# smart_hub_v2.net
KiCad netlist of a schematic drawn in EAGLE
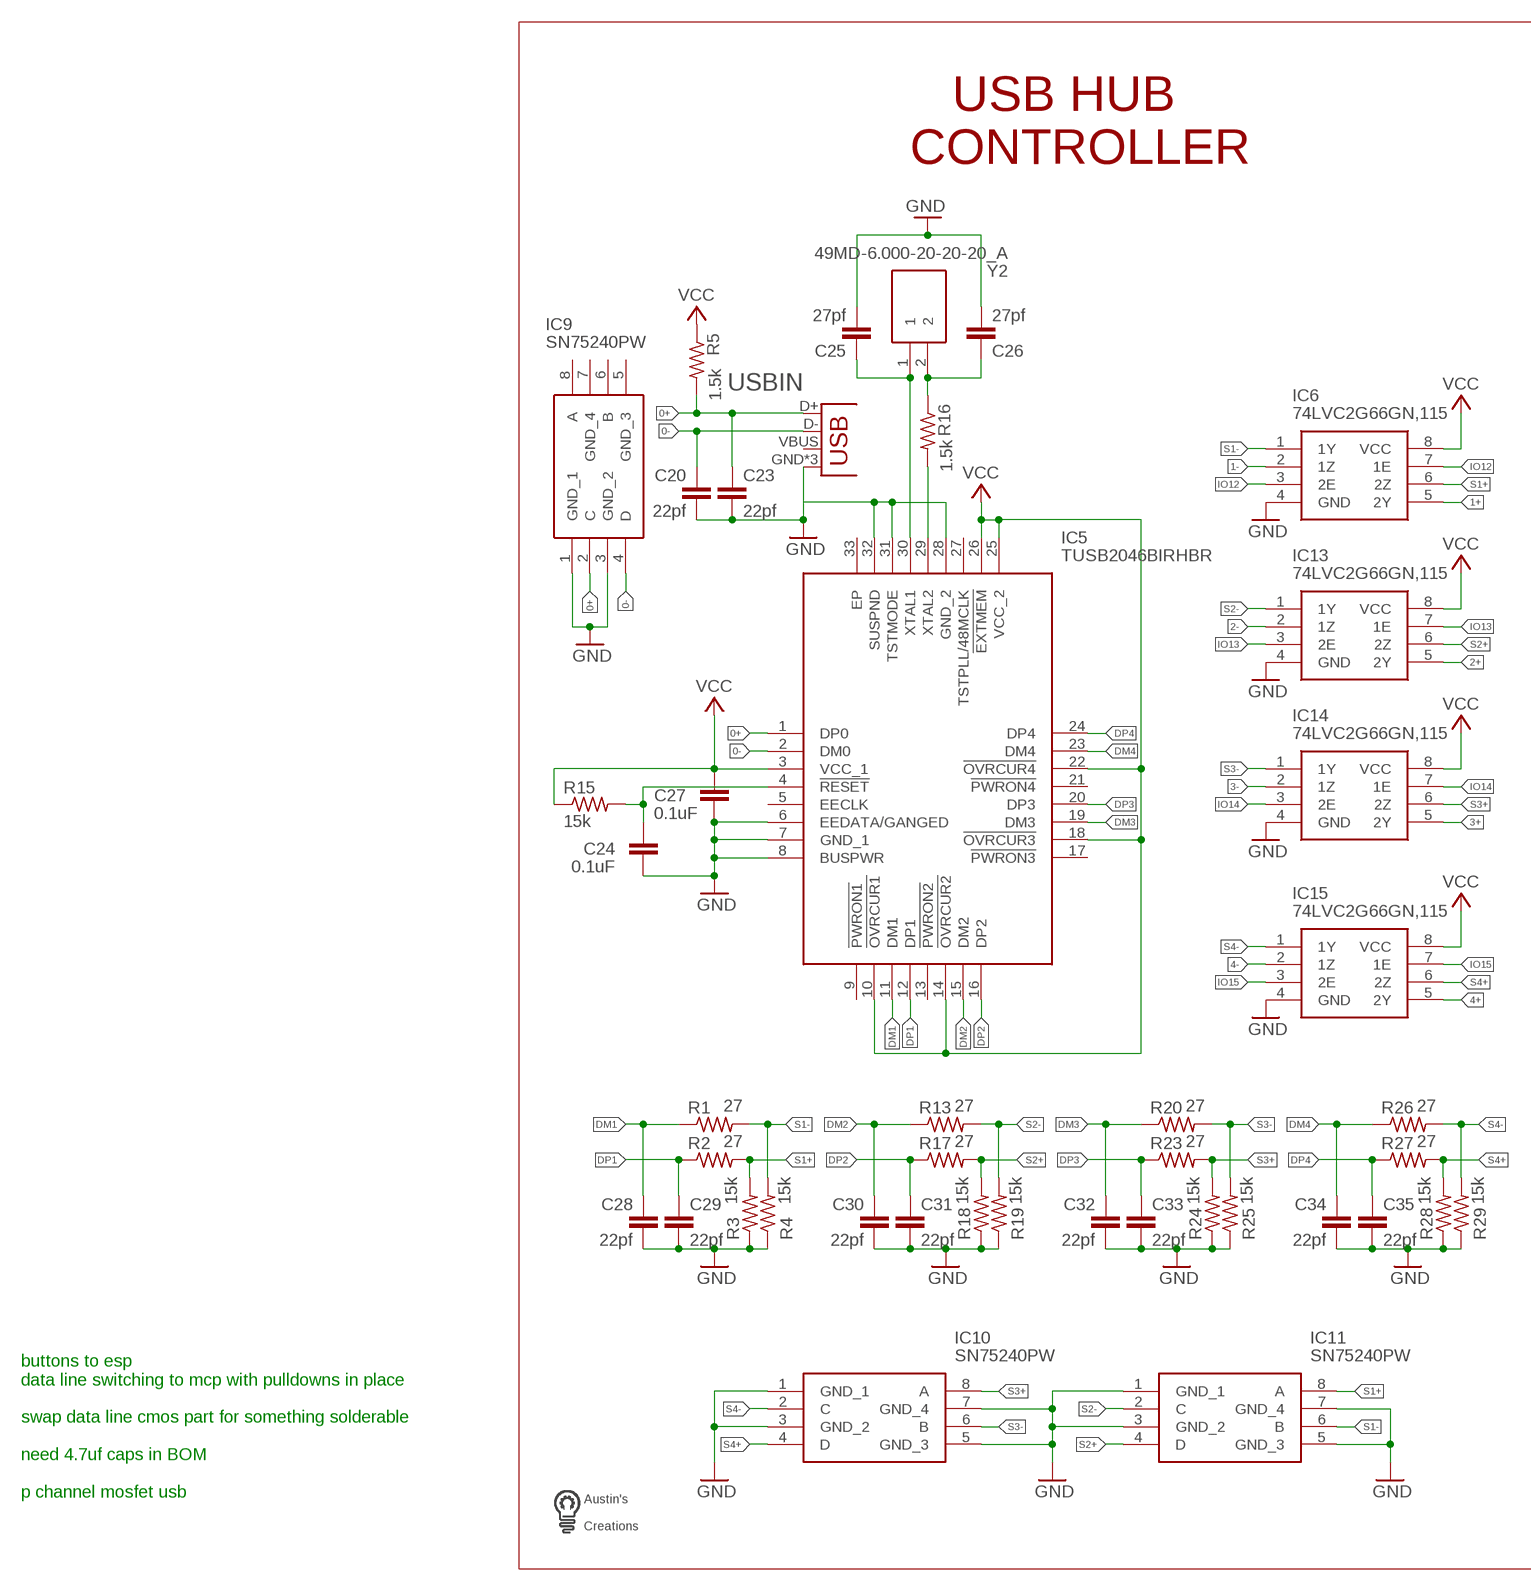
[diagram p0: schematic, sheet 1, part 1 of 2]
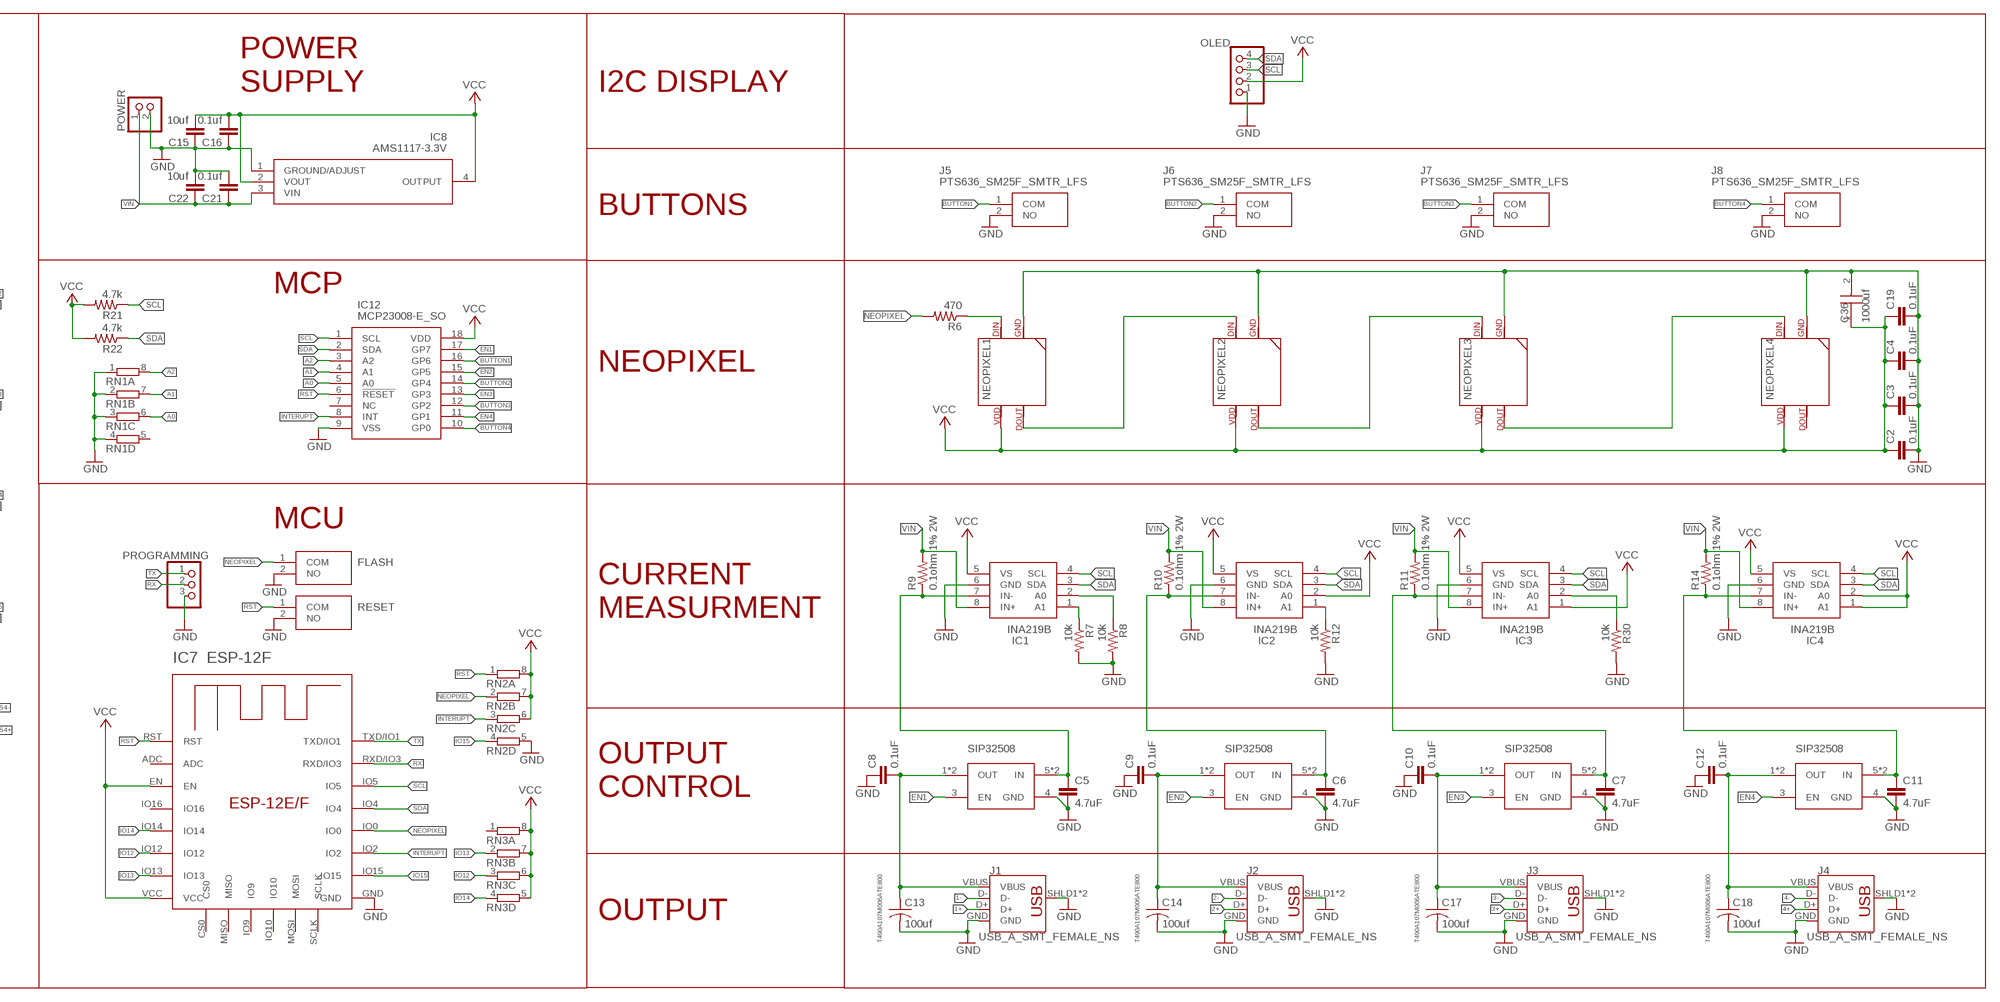
[diagram p1: schematic, sheet 1, part 2 of 2]

(export (version "E")
  (design (tool "Eeschema 10.0.6"))
  (components
    (comp (ref "C2")
      (value "0.1uF")
      (footprint "eagle-import:C0603")
      (libsource (lib "eagle-import") (part "C-EUC0603"))
    )
    (comp (ref "C3")
      (value "0.1uF")
      (footprint "eagle-import:C0603")
      (libsource (lib "eagle-import") (part "C-EUC0603"))
    )
    (comp (ref "C4")
      (value "0.1uF")
      (footprint "eagle-import:C0603")
      (libsource (lib "eagle-import") (part "C-EUC0603"))
    )
    (comp (ref "C5")
      (value "4.7uF")
      (footprint "eagle-import:C0603")
      (libsource (lib "eagle-import") (part "C-EUC0603"))
    )
    (comp (ref "C6")
      (value "4.7uF")
      (footprint "eagle-import:C0603")
      (libsource (lib "eagle-import") (part "C-EUC0603"))
    )
    (comp (ref "C7")
      (value "4.7uF")
      (footprint "eagle-import:C0603")
      (libsource (lib "eagle-import") (part "C-EUC0603"))
    )
    (comp (ref "C8")
      (value "0.1uF")
      (footprint "eagle-import:C0603")
      (libsource (lib "eagle-import") (part "C-EUC0603"))
    )
    (comp (ref "C9")
      (value "0.1uF")
      (footprint "eagle-import:C0603")
      (libsource (lib "eagle-import") (part "C-EUC0603"))
    )
    (comp (ref "C10")
      (value "0.1uF")
      (footprint "eagle-import:C0603")
      (libsource (lib "eagle-import") (part "C-EUC0603"))
    )
    (comp (ref "C11")
      (value "4.7uF")
      (footprint "eagle-import:C0603")
      (libsource (lib "eagle-import") (part "C-EUC0603"))
    )
    (comp (ref "C12")
      (value "0.1uF")
      (footprint "eagle-import:C0603")
      (libsource (lib "eagle-import") (part "C-EUC0603"))
    )
    (comp (ref "C13")
      (value "100uf")
      (footprint "eagle-import:C1206")
      (libsource (lib "eagle-import") (part "C-USC1206"))
    )
    (comp (ref "C14")
      (value "100uf")
      (footprint "eagle-import:C1206")
      (libsource (lib "eagle-import") (part "C-USC1206"))
    )
    (comp (ref "C15")
      (value "10uf")
      (footprint "eagle-import:C0603")
      (libsource (lib "eagle-import") (part "C-EUC0603"))
    )
    (comp (ref "C16")
      (value "0.1uf")
      (footprint "eagle-import:C0603")
      (libsource (lib "eagle-import") (part "C-EUC0603"))
    )
    (comp (ref "C17")
      (value "100uf")
      (footprint "eagle-import:C1206")
      (libsource (lib "eagle-import") (part "C-USC1206"))
    )
    (comp (ref "C18")
      (value "100uf")
      (footprint "eagle-import:C1206")
      (libsource (lib "eagle-import") (part "C-USC1206"))
    )
    (comp (ref "C19")
      (value "0.1uF")
      (footprint "eagle-import:C0603")
      (libsource (lib "eagle-import") (part "C-EUC0603"))
    )
    (comp (ref "C20")
      (value "22pf")
      (footprint "eagle-import:C0603")
      (libsource (lib "eagle-import") (part "C-EUC0603"))
    )
    (comp (ref "C21")
      (value "0.1uf")
      (footprint "eagle-import:C0603")
      (libsource (lib "eagle-import") (part "C-EUC0603"))
    )
    (comp (ref "C22")
      (value "10uf")
      (footprint "eagle-import:C0603")
      (libsource (lib "eagle-import") (part "C-EUC0603"))
    )
    (comp (ref "C23")
      (value "22pf")
      (footprint "eagle-import:C0603")
      (libsource (lib "eagle-import") (part "C-EUC0603"))
    )
    (comp (ref "C24")
      (value "0.1uF")
      (footprint "eagle-import:C0603")
      (libsource (lib "eagle-import") (part "C-EUC0603"))
    )
    (comp (ref "C25")
      (value "27pf")
      (footprint "eagle-import:C0603")
      (libsource (lib "eagle-import") (part "C-EUC0603"))
    )
    (comp (ref "C26")
      (value "27pf")
      (footprint "eagle-import:C0603")
      (libsource (lib "eagle-import") (part "C-EUC0603"))
    )
    (comp (ref "C27")
      (value "0.1uF")
      (footprint "eagle-import:C0603")
      (libsource (lib "eagle-import") (part "C-EUC0603"))
    )
    (comp (ref "C28")
      (value "22pf")
      (footprint "eagle-import:C0603")
      (libsource (lib "eagle-import") (part "C-EUC0603"))
    )
    (comp (ref "C29")
      (value "22pf")
      (footprint "eagle-import:C0603")
      (libsource (lib "eagle-import") (part "C-EUC0603"))
    )
    (comp (ref "C30")
      (value "22pf")
      (footprint "eagle-import:C0603")
      (libsource (lib "eagle-import") (part "C-EUC0603"))
    )
    (comp (ref "C31")
      (value "22pf")
      (footprint "eagle-import:C0603")
      (libsource (lib "eagle-import") (part "C-EUC0603"))
    )
    (comp (ref "C32")
      (value "22pf")
      (footprint "eagle-import:C0603")
      (libsource (lib "eagle-import") (part "C-EUC0603"))
    )
    (comp (ref "C33")
      (value "22pf")
      (footprint "eagle-import:C0603")
      (libsource (lib "eagle-import") (part "C-EUC0603"))
    )
    (comp (ref "C34")
      (value "22pf")
      (footprint "eagle-import:C0603")
      (libsource (lib "eagle-import") (part "C-EUC0603"))
    )
    (comp (ref "C35")
      (value "22pf")
      (footprint "eagle-import:C0603")
      (libsource (lib "eagle-import") (part "C-EUC0603"))
    )
    (comp (ref "C36")
      (value "1000uf")
      (footprint "eagle-import:CAPAE1030X1050N")
      (fields
        (field (name "MANUFACTURER_PART_NUMBER") "EEE-0JA102P")
        (field (name "MOUSER_PART_NUMBER") "667-EEE-0JA102P")
      )
      (libsource (lib "eagle-import") (part "EEE-0JA102P"))
    )
    (comp (ref "FLASH")
      (value "PTS636_SM25F_SMTR_LFS")
      (footprint "eagle-import:PTS636SM25FSMTRLFS")
      (fields
        (field (name "ARROW_PART_NUMBER") "PTS636 SM25F SMTR LFS")
        (field (name "MOUSER_PART_NUMBER") "611-PTS636SM25FSMTRL")
      )
      (libsource (lib "eagle-import") (part "PTS636_SM25F_SMTR_LFS"))
    )
    (comp (ref "IC1")
      (value "INA219B")
      (footprint "eagle-import:SOIC127P600X175-8N")
      (fields
        (field (name "ARROW_PART_NUMBER") "INA219AIDR")
        (field (name "MOUSER_PART_NUMBER") "595-INA219AIDR")
      )
      (libsource (lib "eagle-import") (part "INA219AIDR"))
    )
    (comp (ref "IC2")
      (value "INA219B")
      (footprint "eagle-import:SOIC127P600X175-8N")
      (fields
        (field (name "ARROW_PART_NUMBER") "INA219AIDR")
        (field (name "MOUSER_PART_NUMBER") "595-INA219AIDR")
      )
      (libsource (lib "eagle-import") (part "INA219AIDR"))
    )
    (comp (ref "IC3")
      (value "INA219B")
      (footprint "eagle-import:SOIC127P600X175-8N")
      (fields
        (field (name "ARROW_PART_NUMBER") "INA219AIDR")
        (field (name "MOUSER_PART_NUMBER") "595-INA219AIDR")
      )
      (libsource (lib "eagle-import") (part "INA219AIDR"))
    )
    (comp (ref "IC4")
      (value "INA219B")
      (footprint "eagle-import:SOIC127P600X175-8N")
      (fields
        (field (name "ARROW_PART_NUMBER") "INA219AIDR")
        (field (name "MOUSER_PART_NUMBER") "595-INA219AIDR")
      )
      (libsource (lib "eagle-import") (part "INA219AIDR"))
    )
    (comp (ref "IC5")
      (value "TUSB2046BIRHBR")
      (footprint "eagle-import:QFN50P500X500X100-33N")
      (fields (field (name "MOUSER_PART_NUMBER") "595-TUSB2046BIRHBR"))
      (libsource (lib "eagle-import") (part "TUSB2046BIRHBR"))
    )
    (comp (ref "IC6")
      (value "74LVC2G66GN,115")
      (footprint "eagle-import:74AUP1G74GN115")
      (fields (field (name "MOUSER_PART_NUMBER") "771-74LVC2G66GN115"))
      (libsource (lib "eagle-import") (part "74LVC2G66GN,115"))
    )
    (comp (ref "IC7")
      (value "ESP-12F")
      (footprint "eagle-import:ESP-12E")
      (libsource (lib "eagle-import") (part "ESP-12E/F"))
    )
    (comp (ref "IC8")
      (value "AMS1117-3.3V")
      (footprint "eagle-import:SOT229P700X180-4N")
      (fields (field (name "MANUFACTURER_PART_NUMBER") "ams1117-3.3v"))
      (libsource (lib "eagle-import") (part "AMS1117-3.3V"))
    )
    (comp (ref "IC9")
      (value "SN75240PW")
      (footprint "eagle-import:SOP65P640X120-8N")
      (fields (field (name "MOUSER_PART_NUMBER") "595-SN75240PW"))
      (libsource (lib "eagle-import") (part "SN75240PW"))
    )
    (comp (ref "IC10")
      (value "SN75240PW")
      (footprint "eagle-import:SOP65P640X120-8N")
      (fields (field (name "MOUSER_PART_NUMBER") "595-SN75240PW"))
      (libsource (lib "eagle-import") (part "SN75240PW"))
    )
    (comp (ref "IC11")
      (value "SN75240PW")
      (footprint "eagle-import:SOP65P640X120-8N")
      (fields (field (name "MOUSER_PART_NUMBER") "595-SN75240PW"))
      (libsource (lib "eagle-import") (part "SN75240PW"))
    )
    (comp (ref "IC12")
      (value "MCP23008-E_SO")
      (footprint "eagle-import:SOIC127P1030X265-18N")
      (fields
        (field (name "ARROW_PART_NUMBER") "MCP23008-E/SO")
        (field (name "MOUSER_PART_NUMBER") "579-MCP23008-E/SO")
      )
      (libsource (lib "eagle-import") (part "MCP23008-E_SO"))
    )
    (comp (ref "IC13")
      (value "74LVC2G66GN,115")
      (footprint "eagle-import:74AUP1G74GN115")
      (fields (field (name "MOUSER_PART_NUMBER") "771-74LVC2G66GN115"))
      (libsource (lib "eagle-import") (part "74LVC2G66GN,115"))
    )
    (comp (ref "IC14")
      (value "74LVC2G66GN,115")
      (footprint "eagle-import:74AUP1G74GN115")
      (fields (field (name "MOUSER_PART_NUMBER") "771-74LVC2G66GN115"))
      (libsource (lib "eagle-import") (part "74LVC2G66GN,115"))
    )
    (comp (ref "IC15")
      (value "74LVC2G66GN,115")
      (footprint "eagle-import:74AUP1G74GN115")
      (fields (field (name "MOUSER_PART_NUMBER") "771-74LVC2G66GN115"))
      (libsource (lib "eagle-import") (part "74LVC2G66GN,115"))
    )
    (comp (ref "J1")
      (value "USB_A_SMT_FEMALE_NS")
      (footprint "eagle-import:USB-A-S-NOSILK-FEMALE")
      (libsource (lib "eagle-import") (part "USB_A_SMT_FEMALE_NS"))
    )
    (comp (ref "J2")
      (value "USB_A_SMT_FEMALE_NS")
      (footprint "eagle-import:USB-A-S-NOSILK-FEMALE")
      (libsource (lib "eagle-import") (part "USB_A_SMT_FEMALE_NS"))
    )
    (comp (ref "J3")
      (value "USB_A_SMT_FEMALE_NS")
      (footprint "eagle-import:USB-A-S-NOSILK-FEMALE")
      (libsource (lib "eagle-import") (part "USB_A_SMT_FEMALE_NS"))
    )
    (comp (ref "J4")
      (value "USB_A_SMT_FEMALE_NS")
      (footprint "eagle-import:USB-A-S-NOSILK-FEMALE")
      (libsource (lib "eagle-import") (part "USB_A_SMT_FEMALE_NS"))
    )
    (comp (ref "J5")
      (value "PTS636_SM25F_SMTR_LFS")
      (footprint "eagle-import:PTS636SM25FSMTRLFS")
      (fields
        (field (name "ARROW_PART_NUMBER") "PTS636 SM25F SMTR LFS")
        (field (name "MOUSER_PART_NUMBER") "611-PTS636SM25FSMTRL")
      )
      (libsource (lib "eagle-import") (part "PTS636_SM25F_SMTR_LFS"))
    )
    (comp (ref "J6")
      (value "PTS636_SM25F_SMTR_LFS")
      (footprint "eagle-import:PTS636SM25FSMTRLFS")
      (fields
        (field (name "ARROW_PART_NUMBER") "PTS636 SM25F SMTR LFS")
        (field (name "MOUSER_PART_NUMBER") "611-PTS636SM25FSMTRL")
      )
      (libsource (lib "eagle-import") (part "PTS636_SM25F_SMTR_LFS"))
    )
    (comp (ref "J7")
      (value "PTS636_SM25F_SMTR_LFS")
      (footprint "eagle-import:PTS636SM25FSMTRLFS")
      (fields
        (field (name "ARROW_PART_NUMBER") "PTS636 SM25F SMTR LFS")
        (field (name "MOUSER_PART_NUMBER") "611-PTS636SM25FSMTRL")
      )
      (libsource (lib "eagle-import") (part "PTS636_SM25F_SMTR_LFS"))
    )
    (comp (ref "J8")
      (value "PTS636_SM25F_SMTR_LFS")
      (footprint "eagle-import:PTS636SM25FSMTRLFS")
      (fields
        (field (name "ARROW_PART_NUMBER") "PTS636 SM25F SMTR LFS")
        (field (name "MOUSER_PART_NUMBER") "611-PTS636SM25FSMTRL")
      )
      (libsource (lib "eagle-import") (part "PTS636_SM25F_SMTR_LFS"))
    )
    (comp (ref "NEOPIXEL1")
      (value "SK6812NEOPIXEL5050")
      (footprint "eagle-import:SK6812")
      (libsource (lib "eagle-import") (part "SK68125050NEOPIXEL"))
    )
    (comp (ref "NEOPIXEL2")
      (value "SK6812NEOPIXEL5050")
      (footprint "eagle-import:SK6812")
      (libsource (lib "eagle-import") (part "SK68125050NEOPIXEL"))
    )
    (comp (ref "NEOPIXEL3")
      (value "SK6812NEOPIXEL5050")
      (footprint "eagle-import:SK6812")
      (libsource (lib "eagle-import") (part "SK68125050NEOPIXEL"))
    )
    (comp (ref "NEOPIXEL4")
      (value "SK6812NEOPIXEL5050")
      (footprint "eagle-import:SK6812")
      (libsource (lib "eagle-import") (part "SK68125050NEOPIXEL"))
    )
    (comp (ref "OLED")
      (value "PINHD-1X4")
      (footprint "eagle-import:1X04")
      (libsource (lib "eagle-import") (part "PINHD-1X4"))
    )
    (comp (ref "POWER")
      (value "PINHD-1X2")
      (footprint "eagle-import:1X02")
      (libsource (lib "eagle-import") (part "PINHD-1X2"))
    )
    (comp (ref "PROGRAMMING")
      (value "PINHD-1X3")
      (footprint "eagle-import:1X03")
      (libsource (lib "eagle-import") (part "PINHD-1X3"))
    )
    (comp (ref "R1")
      (value "27")
      (footprint "eagle-import:R0603")
      (libsource (lib "eagle-import") (part "R-US_R0603"))
    )
    (comp (ref "R2")
      (value "27")
      (footprint "eagle-import:R0603")
      (libsource (lib "eagle-import") (part "R-US_R0603"))
    )
    (comp (ref "R3")
      (value "15k")
      (footprint "eagle-import:R0603")
      (libsource (lib "eagle-import") (part "R-US_R0603"))
    )
    (comp (ref "R4")
      (value "15k")
      (footprint "eagle-import:R0603")
      (libsource (lib "eagle-import") (part "R-US_R0603"))
    )
    (comp (ref "R5")
      (value "1.5k")
      (footprint "eagle-import:R0603")
      (libsource (lib "eagle-import") (part "R-US_R0603"))
    )
    (comp (ref "R6")
      (value "470")
      (footprint "eagle-import:R0603")
      (libsource (lib "eagle-import") (part "R-US_R0603"))
    )
    (comp (ref "R7")
      (value "10k")
      (footprint "eagle-import:R0603")
      (libsource (lib "eagle-import") (part "R-US_R0603"))
    )
    (comp (ref "R8")
      (value "10k")
      (footprint "eagle-import:R0603")
      (libsource (lib "eagle-import") (part "R-US_R0603"))
    )
    (comp (ref "R9")
      (value "0.1ohm 1% 2W")
      (footprint "eagle-import:R2512W")
      (libsource (lib "eagle-import") (part "R-US_R2512W"))
    )
    (comp (ref "R10")
      (value "0.1ohm 1% 2W")
      (footprint "eagle-import:R2512W")
      (libsource (lib "eagle-import") (part "R-US_R2512W"))
    )
    (comp (ref "R11")
      (value "0.1ohm 1% 2W")
      (footprint "eagle-import:R2512W")
      (libsource (lib "eagle-import") (part "R-US_R2512W"))
    )
    (comp (ref "R12")
      (value "10k")
      (footprint "eagle-import:R0603")
      (libsource (lib "eagle-import") (part "R-US_R0603"))
    )
    (comp (ref "R13")
      (value "27")
      (footprint "eagle-import:R0603")
      (libsource (lib "eagle-import") (part "R-US_R0603"))
    )
    (comp (ref "R14")
      (value "0.1ohm 1% 2W")
      (footprint "eagle-import:R2512W")
      (libsource (lib "eagle-import") (part "R-US_R2512W"))
    )
    (comp (ref "R15")
      (value "15k")
      (footprint "eagle-import:R0603")
      (libsource (lib "eagle-import") (part "R-US_R0603"))
    )
    (comp (ref "R16")
      (value "1.5k")
      (footprint "eagle-import:R0603")
      (libsource (lib "eagle-import") (part "R-US_R0603"))
    )
    (comp (ref "R17")
      (value "27")
      (footprint "eagle-import:R0603")
      (libsource (lib "eagle-import") (part "R-US_R0603"))
    )
    (comp (ref "R18")
      (value "15k")
      (footprint "eagle-import:R0603")
      (libsource (lib "eagle-import") (part "R-US_R0603"))
    )
    (comp (ref "R19")
      (value "15k")
      (footprint "eagle-import:R0603")
      (libsource (lib "eagle-import") (part "R-US_R0603"))
    )
    (comp (ref "R20")
      (value "27")
      (footprint "eagle-import:R0603")
      (libsource (lib "eagle-import") (part "R-US_R0603"))
    )
    (comp (ref "R21")
      (value "4.7k")
      (footprint "eagle-import:R0603")
      (libsource (lib "eagle-import") (part "R-US_R0603"))
    )
    (comp (ref "R22")
      (value "4.7k")
      (footprint "eagle-import:R0603")
      (libsource (lib "eagle-import") (part "R-US_R0603"))
    )
    (comp (ref "R23")
      (value "27")
      (footprint "eagle-import:R0603")
      (libsource (lib "eagle-import") (part "R-US_R0603"))
    )
    (comp (ref "R24")
      (value "15k")
      (footprint "eagle-import:R0603")
      (libsource (lib "eagle-import") (part "R-US_R0603"))
    )
    (comp (ref "R25")
      (value "15k")
      (footprint "eagle-import:R0603")
      (libsource (lib "eagle-import") (part "R-US_R0603"))
    )
    (comp (ref "R26")
      (value "27")
      (footprint "eagle-import:R0603")
      (libsource (lib "eagle-import") (part "R-US_R0603"))
    )
    (comp (ref "R27")
      (value "27")
      (footprint "eagle-import:R0603")
      (libsource (lib "eagle-import") (part "R-US_R0603"))
    )
    (comp (ref "R28")
      (value "15k")
      (footprint "eagle-import:R0603")
      (libsource (lib "eagle-import") (part "R-US_R0603"))
    )
    (comp (ref "R29")
      (value "15k")
      (footprint "eagle-import:R0603")
      (libsource (lib "eagle-import") (part "R-US_R0603"))
    )
    (comp (ref "R30")
      (value "10k")
      (footprint "eagle-import:R0603")
      (libsource (lib "eagle-import") (part "R-US_R0603"))
    )
    (comp (ref "RESET")
      (value "PTS636_SM25F_SMTR_LFS")
      (footprint "eagle-import:PTS636SM25FSMTRLFS")
      (fields
        (field (name "ARROW_PART_NUMBER") "PTS636 SM25F SMTR LFS")
        (field (name "MOUSER_PART_NUMBER") "611-PTS636SM25FSMTRL")
      )
      (libsource (lib "eagle-import") (part "PTS636_SM25F_SMTR_LFS"))
    )
    (comp (ref "RN1")
      (value "4R-N0603-ARC")
      (footprint "eagle-import:0603-ARC")
      (libsource (lib "eagle-import") (part "4R-N0603-ARC"))
    )
    (comp (ref "RN2")
      (value "4R-N0603-ARC")
      (footprint "eagle-import:0603-ARC")
      (libsource (lib "eagle-import") (part "4R-N0603-ARC"))
    )
    (comp (ref "RN3")
      (value "4R-N0603-ARC")
      (footprint "eagle-import:0603-ARC")
      (libsource (lib "eagle-import") (part "4R-N0603-ARC"))
    )
    (comp (ref "U$1")
      (value "LOGOMASSIVE")
      (footprint "eagle-import:LOGOMASSIVE")
      (libsource (lib "eagle-import") (part "LOGOMASSIVE"))
    )
    (comp (ref "U$3")
      (value "SIP32508")
      (footprint "eagle-import:SOT23-6")
      (libsource (lib "eagle-import") (part "SIP32508"))
    )
    (comp (ref "U$4")
      (value "SIP32508")
      (footprint "eagle-import:SOT23-6")
      (libsource (lib "eagle-import") (part "SIP32508"))
    )
    (comp (ref "U$5")
      (value "SIP32508")
      (footprint "eagle-import:SOT23-6")
      (libsource (lib "eagle-import") (part "SIP32508"))
    )
    (comp (ref "U$8")
      (value "SIP32508")
      (footprint "eagle-import:SOT23-6")
      (libsource (lib "eagle-import") (part "SIP32508"))
    )
    (comp (ref "USBIN")
      (value "USB-MICROB")
      (footprint "eagle-import:USB-MICROB")
      (libsource (lib "eagle-import") (part "USB-MICROB"))
    )
    (comp (ref "Y2")
      (value "49MD-6.000-20-20-20_A")
      (footprint "eagle-import:49MD6000202020A")
      (fields (field (name "MANUFACTURER_PART_NUMBER") "49MD-6.000-20-20-20/A"))
      (libsource (lib "eagle-import") (part "49MD-6.000-20-20-20_A"))
    )
  )
  (nets
    (net (code "1") (name "0+") (class "Default")
      (node (ref "C23") (pin "1") (pinfunction "1_1") (pintype "passive"))
      (node (ref "IC5") (pin "1") (pinfunction "DP0_1") (pintype "bidirectional"))
      (node (ref "IC9") (pin "2") (pinfunction "C_2") (pintype "bidirectional"))
      (node (ref "R5") (pin "2") (pinfunction "2_2") (pintype "passive"))
      (node (ref "USBIN") (pin "D+") (pinfunction "D+_D+") (pintype "bidirectional"))
    )
    (net (code "2") (name "0-") (class "Default")
      (node (ref "C20") (pin "1") (pinfunction "1_1") (pintype "passive"))
      (node (ref "IC5") (pin "2") (pinfunction "DM0_2") (pintype "bidirectional"))
      (node (ref "IC9") (pin "4") (pinfunction "D_4") (pintype "bidirectional"))
      (node (ref "USBIN") (pin "D-") (pinfunction "D-_D-") (pintype "bidirectional"))
    )
    (net (code "3") (name "1+") (class "Default")
      (node (ref "IC6") (pin "5") (pinfunction "2Y_5") (pintype "bidirectional"))
      (node (ref "J1") (pin "D+") (pinfunction "D+_D+") (pintype "bidirectional"))
    )
    (net (code "4") (name "1-") (class "Default")
      (node (ref "IC6") (pin "2") (pinfunction "1Z_2") (pintype "bidirectional"))
      (node (ref "J1") (pin "D-") (pinfunction "D-_D-") (pintype "bidirectional"))
    )
    (net (code "5") (name "2+") (class "Default")
      (node (ref "IC13") (pin "5") (pinfunction "2Y_5") (pintype "bidirectional"))
      (node (ref "J2") (pin "D+") (pinfunction "D+_D+") (pintype "bidirectional"))
    )
    (net (code "6") (name "2-") (class "Default")
      (node (ref "IC13") (pin "2") (pinfunction "1Z_2") (pintype "bidirectional"))
      (node (ref "J2") (pin "D-") (pinfunction "D-_D-") (pintype "bidirectional"))
    )
    (net (code "7") (name "3+") (class "Default")
      (node (ref "IC14") (pin "5") (pinfunction "2Y_5") (pintype "bidirectional"))
      (node (ref "J3") (pin "D+") (pinfunction "D+_D+") (pintype "bidirectional"))
    )
    (net (code "8") (name "3-") (class "Default")
      (node (ref "IC14") (pin "2") (pinfunction "1Z_2") (pintype "bidirectional"))
      (node (ref "J3") (pin "D-") (pinfunction "D-_D-") (pintype "bidirectional"))
    )
    (net (code "9") (name "4+") (class "Default")
      (node (ref "IC15") (pin "5") (pinfunction "2Y_5") (pintype "bidirectional"))
      (node (ref "J4") (pin "D+") (pinfunction "D+_D+") (pintype "bidirectional"))
    )
    (net (code "10") (name "4-") (class "Default")
      (node (ref "IC15") (pin "2") (pinfunction "1Z_2") (pintype "bidirectional"))
      (node (ref "J4") (pin "D-") (pinfunction "D-_D-") (pintype "bidirectional"))
    )
    (net (code "11") (name "A0") (class "Default")
      (node (ref "IC12") (pin "5") (pinfunction "A0_5") (pintype "bidirectional"))
      (node (ref "RN1") (pin "6") (pinfunction "2_6") (pintype "passive"))
    )
    (net (code "12") (name "A1") (class "Default")
      (node (ref "IC12") (pin "4") (pinfunction "A1_4") (pintype "bidirectional"))
      (node (ref "RN1") (pin "7") (pinfunction "2_7") (pintype "passive"))
    )
    (net (code "13") (name "A2") (class "Default")
      (node (ref "IC12") (pin "3") (pinfunction "A2_3") (pintype "bidirectional"))
      (node (ref "RN1") (pin "8") (pinfunction "2_8") (pintype "passive"))
    )
    (net (code "14") (name "BUTTON1") (class "Default")
      (node (ref "IC12") (pin "16") (pinfunction "GP6_16") (pintype "bidirectional"))
      (node (ref "J5") (pin "1") (pinfunction "COM_1") (pintype "bidirectional"))
    )
    (net (code "15") (name "BUTTON2") (class "Default")
      (node (ref "IC12") (pin "14") (pinfunction "GP4_14") (pintype "bidirectional"))
      (node (ref "J6") (pin "1") (pinfunction "COM_1") (pintype "bidirectional"))
    )
    (net (code "16") (name "BUTTON3") (class "Default")
      (node (ref "IC12") (pin "12") (pinfunction "GP2_12") (pintype "bidirectional"))
      (node (ref "J7") (pin "1") (pinfunction "COM_1") (pintype "bidirectional"))
    )
    (net (code "17") (name "BUTTON4") (class "Default")
      (node (ref "IC12") (pin "10") (pinfunction "GP0_10") (pintype "bidirectional"))
      (node (ref "J8") (pin "1") (pinfunction "COM_1") (pintype "bidirectional"))
    )
    (net (code "18") (name "DM1") (class "Default")
      (node (ref "C28") (pin "1") (pinfunction "1_1") (pintype "passive"))
      (node (ref "IC5") (pin "11") (pinfunction "DM1_11") (pintype "bidirectional"))
      (node (ref "R1") (pin "1") (pinfunction "1_1") (pintype "passive"))
    )
    (net (code "19") (name "DM2") (class "Default")
      (node (ref "C30") (pin "1") (pinfunction "1_1") (pintype "passive"))
      (node (ref "IC5") (pin "15") (pinfunction "DM2_15") (pintype "bidirectional"))
      (node (ref "R13") (pin "1") (pinfunction "1_1") (pintype "passive"))
    )
    (net (code "20") (name "DM3") (class "Default")
      (node (ref "C32") (pin "1") (pinfunction "1_1") (pintype "passive"))
      (node (ref "IC5") (pin "19") (pinfunction "DM3_19") (pintype "bidirectional"))
      (node (ref "R20") (pin "1") (pinfunction "1_1") (pintype "passive"))
    )
    (net (code "21") (name "DM4") (class "Default")
      (node (ref "C34") (pin "1") (pinfunction "1_1") (pintype "passive"))
      (node (ref "IC5") (pin "23") (pinfunction "DM4_23") (pintype "bidirectional"))
      (node (ref "R26") (pin "1") (pinfunction "1_1") (pintype "passive"))
    )
    (net (code "22") (name "DP1") (class "Default")
      (node (ref "C29") (pin "1") (pinfunction "1_1") (pintype "passive"))
      (node (ref "IC5") (pin "12") (pinfunction "DP1_12") (pintype "bidirectional"))
      (node (ref "R2") (pin "1") (pinfunction "1_1") (pintype "passive"))
    )
    (net (code "23") (name "DP2") (class "Default")
      (node (ref "C31") (pin "1") (pinfunction "1_1") (pintype "passive"))
      (node (ref "IC5") (pin "16") (pinfunction "DP2_16") (pintype "bidirectional"))
      (node (ref "R17") (pin "1") (pinfunction "1_1") (pintype "passive"))
    )
    (net (code "24") (name "DP3") (class "Default")
      (node (ref "C33") (pin "1") (pinfunction "1_1") (pintype "passive"))
      (node (ref "IC5") (pin "20") (pinfunction "DP3_20") (pintype "bidirectional"))
      (node (ref "R23") (pin "1") (pinfunction "1_1") (pintype "passive"))
    )
    (net (code "25") (name "DP4") (class "Default")
      (node (ref "C35") (pin "1") (pinfunction "1_1") (pintype "passive"))
      (node (ref "IC5") (pin "24") (pinfunction "DP4_24") (pintype "bidirectional"))
      (node (ref "R27") (pin "1") (pinfunction "1_1") (pintype "passive"))
    )
    (net (code "26") (name "EN1") (class "Default")
      (node (ref "IC12") (pin "17") (pinfunction "GP7_17") (pintype "bidirectional"))
      (node (ref "U$3") (pin "3") (pinfunction "EN_3") (pintype "bidirectional"))
    )
    (net (code "27") (name "EN2") (class "Default")
      (node (ref "IC12") (pin "15") (pinfunction "GP5_15") (pintype "bidirectional"))
      (node (ref "U$4") (pin "3") (pinfunction "EN_3") (pintype "bidirectional"))
    )
    (net (code "28") (name "EN3") (class "Default")
      (node (ref "IC12") (pin "13") (pinfunction "GP3_13") (pintype "bidirectional"))
      (node (ref "U$5") (pin "3") (pinfunction "EN_3") (pintype "bidirectional"))
    )
    (net (code "29") (name "EN4") (class "Default")
      (node (ref "IC12") (pin "11") (pinfunction "GP1_11") (pintype "bidirectional"))
      (node (ref "U$8") (pin "3") (pinfunction "EN_3") (pintype "bidirectional"))
    )
    (net (code "30") (name "GND") (class "Default")
      (node (ref "C10") (pin "1") (pinfunction "1_1") (pintype "passive"))
      (node (ref "C11") (pin "2") (pinfunction "2_2") (pintype "passive"))
      (node (ref "C12") (pin "1") (pinfunction "1_1") (pintype "passive"))
      (node (ref "C13") (pin "2") (pinfunction "2_2") (pintype "passive"))
      (node (ref "C14") (pin "2") (pinfunction "2_2") (pintype "passive"))
      (node (ref "C15") (pin "1") (pinfunction "1_1") (pintype "passive"))
      (node (ref "C16") (pin "1") (pinfunction "1_1") (pintype "passive"))
      (node (ref "C17") (pin "2") (pinfunction "2_2") (pintype "passive"))
      (node (ref "C18") (pin "2") (pinfunction "2_2") (pintype "passive"))
      (node (ref "C19") (pin "2") (pinfunction "2_2") (pintype "passive"))
      (node (ref "C2") (pin "2") (pinfunction "2_2") (pintype "passive"))
      (node (ref "C20") (pin "2") (pinfunction "2_2") (pintype "passive"))
      (node (ref "C21") (pin "2") (pinfunction "2_2") (pintype "passive"))
      (node (ref "C22") (pin "2") (pinfunction "2_2") (pintype "passive"))
      (node (ref "C23") (pin "2") (pinfunction "2_2") (pintype "passive"))
      (node (ref "C24") (pin "2") (pinfunction "2_2") (pintype "passive"))
      (node (ref "C25") (pin "2") (pinfunction "2_2") (pintype "passive"))
      (node (ref "C26") (pin "2") (pinfunction "2_2") (pintype "passive"))
      (node (ref "C27") (pin "2") (pinfunction "2_2") (pintype "passive"))
      (node (ref "C28") (pin "2") (pinfunction "2_2") (pintype "passive"))
      (node (ref "C29") (pin "2") (pinfunction "2_2") (pintype "passive"))
      (node (ref "C3") (pin "2") (pinfunction "2_2") (pintype "passive"))
      (node (ref "C30") (pin "2") (pinfunction "2_2") (pintype "passive"))
      (node (ref "C31") (pin "2") (pinfunction "2_2") (pintype "passive"))
      (node (ref "C32") (pin "2") (pinfunction "2_2") (pintype "passive"))
      (node (ref "C33") (pin "2") (pinfunction "2_2") (pintype "passive"))
      (node (ref "C34") (pin "2") (pinfunction "2_2") (pintype "passive"))
      (node (ref "C35") (pin "2") (pinfunction "2_2") (pintype "passive"))
      (node (ref "C36") (pin "2") (pinfunction "-_2") (pintype "bidirectional"))
      (node (ref "C4") (pin "2") (pinfunction "2_2") (pintype "passive"))
      (node (ref "C5") (pin "2") (pinfunction "2_2") (pintype "passive"))
      (node (ref "C6") (pin "2") (pinfunction "2_2") (pintype "passive"))
      (node (ref "C7") (pin "2") (pinfunction "2_2") (pintype "passive"))
      (node (ref "C8") (pin "1") (pinfunction "1_1") (pintype "passive"))
      (node (ref "C9") (pin "1") (pinfunction "1_1") (pintype "passive"))
      (node (ref "FLASH") (pin "2") (pinfunction "NO_2") (pintype "bidirectional"))
      (node (ref "IC1") (pin "6") (pinfunction "GND_6") (pintype "bidirectional"))
      (node (ref "IC10") (pin "1") (pinfunction "GND_1_1") (pintype "bidirectional"))
      (node (ref "IC10") (pin "3") (pinfunction "GND_2_3") (pintype "bidirectional"))
      (node (ref "IC10") (pin "5") (pinfunction "GND_3_5") (pintype "bidirectional"))
      (node (ref "IC10") (pin "7") (pinfunction "GND_4_7") (pintype "bidirectional"))
      (node (ref "IC11") (pin "1") (pinfunction "GND_1_1") (pintype "bidirectional"))
      (node (ref "IC11") (pin "3") (pinfunction "GND_2_3") (pintype "bidirectional"))
      (node (ref "IC11") (pin "5") (pinfunction "GND_3_5") (pintype "bidirectional"))
      (node (ref "IC11") (pin "7") (pinfunction "GND_4_7") (pintype "bidirectional"))
      (node (ref "IC12") (pin "9") (pinfunction "VSS_9") (pintype "bidirectional"))
      (node (ref "IC13") (pin "4") (pinfunction "GND_4") (pintype "bidirectional"))
      (node (ref "IC14") (pin "4") (pinfunction "GND_4") (pintype "bidirectional"))
      (node (ref "IC15") (pin "4") (pinfunction "GND_4") (pintype "bidirectional"))
      (node (ref "IC2") (pin "6") (pinfunction "GND_6") (pintype "bidirectional"))
      (node (ref "IC3") (pin "6") (pinfunction "GND_6") (pintype "bidirectional"))
      (node (ref "IC4") (pin "6") (pinfunction "GND_6") (pintype "bidirectional"))
      (node (ref "IC5") (pin "28") (pinfunction "GND_2_28") (pintype "bidirectional"))
      (node (ref "IC5") (pin "31") (pinfunction "TSTMODE_31") (pintype "bidirectional"))
      (node (ref "IC5") (pin "32") (pinfunction "SUSPND_32") (pintype "bidirectional"))
      (node (ref "IC5") (pin "6") (pinfunction "EEDATA/GANGED_6") (pintype "bidirectional"))
      (node (ref "IC5") (pin "7") (pinfunction "GND_1_7") (pintype "bidirectional"))
      (node (ref "IC5") (pin "8") (pinfunction "BUSPWR_8") (pintype "bidirectional"))
      (node (ref "IC6") (pin "4") (pinfunction "GND_4") (pintype "bidirectional"))
      (node (ref "IC7") (pin "GND") (pinfunction "GND_GND") (pintype "power_in"))
      (node (ref "IC8") (pin "1") (pinfunction "GROUND/ADJUST_1") (pintype "bidirectional"))
      (node (ref "IC9") (pin "1") (pinfunction "GND_1_1") (pintype "bidirectional"))
      (node (ref "IC9") (pin "3") (pinfunction "GND_2_3") (pintype "bidirectional"))
      (node (ref "J1") (pin "GND") (pinfunction "GND_GND") (pintype "power_in"))
      (node (ref "J1") (pin "SHLD1") (pinfunction "SHIELD_SHLD1") (pintype "bidirectional"))
      (node (ref "J1") (pin "SHLD2") (pinfunction "SHIELD_SHLD2") (pintype "bidirectional"))
      (node (ref "J2") (pin "GND") (pinfunction "GND_GND") (pintype "power_in"))
      (node (ref "J2") (pin "SHLD1") (pinfunction "SHIELD_SHLD1") (pintype "bidirectional"))
      (node (ref "J2") (pin "SHLD2") (pinfunction "SHIELD_SHLD2") (pintype "bidirectional"))
      (node (ref "J3") (pin "GND") (pinfunction "GND_GND") (pintype "power_in"))
      (node (ref "J3") (pin "SHLD1") (pinfunction "SHIELD_SHLD1") (pintype "bidirectional"))
      (node (ref "J3") (pin "SHLD2") (pinfunction "SHIELD_SHLD2") (pintype "bidirectional"))
      (node (ref "J4") (pin "GND") (pinfunction "GND_GND") (pintype "power_in"))
      (node (ref "J4") (pin "SHLD1") (pinfunction "SHIELD_SHLD1") (pintype "bidirectional"))
      (node (ref "J4") (pin "SHLD2") (pinfunction "SHIELD_SHLD2") (pintype "bidirectional"))
      (node (ref "J5") (pin "2") (pinfunction "NO_2") (pintype "bidirectional"))
      (node (ref "J6") (pin "2") (pinfunction "NO_2") (pintype "bidirectional"))
      (node (ref "J7") (pin "2") (pinfunction "NO_2") (pintype "bidirectional"))
      (node (ref "J8") (pin "2") (pinfunction "NO_2") (pintype "bidirectional"))
      (node (ref "NEOPIXEL1") (pin "3") (pinfunction "GND_3") (pintype "bidirectional"))
      (node (ref "NEOPIXEL2") (pin "3") (pinfunction "GND_3") (pintype "bidirectional"))
      (node (ref "NEOPIXEL3") (pin "3") (pinfunction "GND_3") (pintype "bidirectional"))
      (node (ref "NEOPIXEL4") (pin "3") (pinfunction "GND_3") (pintype "bidirectional"))
      (node (ref "OLED") (pin "1") (pinfunction "1_1") (pintype "passive"))
      (node (ref "POWER") (pin "2") (pinfunction "2_2") (pintype "passive"))
      (node (ref "PROGRAMMING") (pin "3") (pinfunction "3_3") (pintype "passive"))
      (node (ref "R12") (pin "2") (pinfunction "2_2") (pintype "passive"))
      (node (ref "R18") (pin "1") (pinfunction "1_1") (pintype "passive"))
      (node (ref "R19") (pin "1") (pinfunction "1_1") (pintype "passive"))
      (node (ref "R24") (pin "1") (pinfunction "1_1") (pintype "passive"))
      (node (ref "R25") (pin "1") (pinfunction "1_1") (pintype "passive"))
      (node (ref "R28") (pin "1") (pinfunction "1_1") (pintype "passive"))
      (node (ref "R29") (pin "1") (pinfunction "1_1") (pintype "passive"))
      (node (ref "R3") (pin "1") (pinfunction "1_1") (pintype "passive"))
      (node (ref "R30") (pin "2") (pinfunction "2_2") (pintype "passive"))
      (node (ref "R4") (pin "1") (pinfunction "1_1") (pintype "passive"))
      (node (ref "R7") (pin "2") (pinfunction "2_2") (pintype "passive"))
      (node (ref "R8") (pin "2") (pinfunction "2_2") (pintype "passive"))
      (node (ref "RESET") (pin "2") (pinfunction "NO_2") (pintype "bidirectional"))
      (node (ref "RN1") (pin "1") (pinfunction "1_1") (pintype "passive"))
      (node (ref "RN1") (pin "2") (pinfunction "1_2") (pintype "passive"))
      (node (ref "RN1") (pin "3") (pinfunction "1_3") (pintype "passive"))
      (node (ref "RN1") (pin "4") (pinfunction "1_4") (pintype "passive"))
      (node (ref "RN2") (pin "5") (pinfunction "2_5") (pintype "passive"))
      (node (ref "U$3") (pin "4") (pinfunction "GND_4") (pintype "bidirectional"))
      (node (ref "U$4") (pin "4") (pinfunction "GND_4") (pintype "bidirectional"))
      (node (ref "U$5") (pin "4") (pinfunction "GND_4") (pintype "bidirectional"))
      (node (ref "U$8") (pin "4") (pinfunction "GND_4") (pintype "bidirectional"))
      (node (ref "USBIN") (pin "GND") (pinfunction "GND_GND") (pintype "bidirectional"))
      (node (ref "USBIN") (pin "MT1") (pinfunction "GND_MT1") (pintype "bidirectional"))
      (node (ref "USBIN") (pin "MT2") (pinfunction "GND_MT2") (pintype "bidirectional"))
    )
    (net (code "31") (name "INTERUPT") (class "Default")
      (node (ref "IC12") (pin "8") (pinfunction "INT_8") (pintype "bidirectional"))
      (node (ref "IC7") (pin "IO2") (pinfunction "IO2_IO2") (pintype "bidirectional"))
      (node (ref "RN2") (pin "3") (pinfunction "1_3") (pintype "passive"))
    )
    (net (code "32") (name "IO12") (class "Default")
      (node (ref "IC6") (pin "3") (pinfunction "2E_3") (pintype "bidirectional"))
      (node (ref "IC6") (pin "7") (pinfunction "1E_7") (pintype "bidirectional"))
      (node (ref "IC7") (pin "IO12") (pinfunction "IO12_IO12") (pintype "bidirectional"))
      (node (ref "RN3") (pin "3") (pinfunction "1_3") (pintype "passive"))
    )
    (net (code "33") (name "IO13") (class "Default")
      (node (ref "IC13") (pin "3") (pinfunction "2E_3") (pintype "bidirectional"))
      (node (ref "IC13") (pin "7") (pinfunction "1E_7") (pintype "bidirectional"))
      (node (ref "IC7") (pin "IO13") (pinfunction "IO13_IO13") (pintype "bidirectional"))
      (node (ref "RN3") (pin "2") (pinfunction "1_2") (pintype "passive"))
    )
    (net (code "34") (name "IO14") (class "Default")
      (node (ref "IC14") (pin "3") (pinfunction "2E_3") (pintype "bidirectional"))
      (node (ref "IC14") (pin "7") (pinfunction "1E_7") (pintype "bidirectional"))
      (node (ref "IC7") (pin "IO14") (pinfunction "IO14_IO14") (pintype "bidirectional"))
      (node (ref "RN3") (pin "4") (pinfunction "1_4") (pintype "passive"))
    )
    (net (code "35") (name "IO15") (class "Default")
      (node (ref "IC15") (pin "3") (pinfunction "2E_3") (pintype "bidirectional"))
      (node (ref "IC15") (pin "7") (pinfunction "1E_7") (pintype "bidirectional"))
      (node (ref "IC7") (pin "IO15") (pinfunction "IO15_IO15") (pintype "bidirectional"))
      (node (ref "RN2") (pin "4") (pinfunction "1_4") (pintype "passive"))
    )
    (net (code "36") (name "NEOPIXEL") (class "Default")
      (node (ref "FLASH") (pin "1") (pinfunction "COM_1") (pintype "bidirectional"))
      (node (ref "IC7") (pin "IO0") (pinfunction "IO0_IO0") (pintype "bidirectional"))
      (node (ref "R6") (pin "2") (pinfunction "2_2") (pintype "passive"))
      (node (ref "RN2") (pin "2") (pinfunction "1_2") (pintype "passive"))
    )
    (net (code "37") (name "Net-(C10-Pad2)") (class "Default")
      (node (ref "C10") (pin "2") (pinfunction "2_2") (pintype "passive"))
      (node (ref "C17") (pin "1") (pinfunction "1_1") (pintype "passive"))
      (node (ref "J3") (pin "VBUS") (pinfunction "VBUS_VBUS") (pintype "power_in"))
      (node (ref "U$5") (pin "1") (pinfunction "OUT_1") (pintype "bidirectional"))
      (node (ref "U$5") (pin "2") (pinfunction "OUT_2") (pintype "bidirectional"))
    )
    (net (code "38") (name "Net-(C12-Pad2)") (class "Default")
      (node (ref "C12") (pin "2") (pinfunction "2_2") (pintype "passive"))
      (node (ref "C18") (pin "1") (pinfunction "1_1") (pintype "passive"))
      (node (ref "J4") (pin "VBUS") (pinfunction "VBUS_VBUS") (pintype "power_in"))
      (node (ref "U$8") (pin "1") (pinfunction "OUT_1") (pintype "bidirectional"))
      (node (ref "U$8") (pin "2") (pinfunction "OUT_2") (pintype "bidirectional"))
    )
    (net (code "39") (name "Net-(C13-Pad1)") (class "Default")
      (node (ref "C13") (pin "1") (pinfunction "1_1") (pintype "passive"))
      (node (ref "C8") (pin "2") (pinfunction "2_2") (pintype "passive"))
      (node (ref "J1") (pin "VBUS") (pinfunction "VBUS_VBUS") (pintype "power_in"))
      (node (ref "U$3") (pin "1") (pinfunction "OUT_1") (pintype "bidirectional"))
      (node (ref "U$3") (pin "2") (pinfunction "OUT_2") (pintype "bidirectional"))
    )
    (net (code "40") (name "Net-(C14-Pad1)") (class "Default")
      (node (ref "C14") (pin "1") (pinfunction "1_1") (pintype "passive"))
      (node (ref "C9") (pin "2") (pinfunction "2_2") (pintype "passive"))
      (node (ref "J2") (pin "VBUS") (pinfunction "VBUS_VBUS") (pintype "power_in"))
      (node (ref "U$4") (pin "1") (pinfunction "OUT_1") (pintype "bidirectional"))
      (node (ref "U$4") (pin "2") (pinfunction "OUT_2") (pintype "bidirectional"))
    )
    (net (code "41") (name "Net-(C26-Pad1)") (class "Default")
      (node (ref "C26") (pin "1") (pinfunction "1_1") (pintype "passive"))
      (node (ref "R16") (pin "1") (pinfunction "1_1") (pintype "passive"))
      (node (ref "Y2") (pin "2") (pinfunction "2_2") (pintype "bidirectional"))
    )
    (net (code "42") (name "Net-(IC1-A0)") (class "Default")
      (node (ref "IC1") (pin "2") (pinfunction "A0_2") (pintype "bidirectional"))
      (node (ref "R8") (pin "1") (pinfunction "1_1") (pintype "passive"))
    )
    (net (code "43") (name "Net-(IC1-A1)") (class "Default")
      (node (ref "IC1") (pin "1") (pinfunction "A1_1") (pintype "bidirectional"))
      (node (ref "R7") (pin "1") (pinfunction "1_1") (pintype "passive"))
    )
    (net (code "44") (name "Net-(IC1-IN-)") (class "Default")
      (node (ref "C5") (pin "1") (pinfunction "1_1") (pintype "passive"))
      (node (ref "IC1") (pin "7") (pinfunction "IN-_7") (pintype "bidirectional"))
      (node (ref "R9") (pin "1") (pinfunction "1_1") (pintype "passive"))
      (node (ref "U$3") (pin "5") (pinfunction "IN_5") (pintype "bidirectional"))
      (node (ref "U$3") (pin "6") (pinfunction "IN_6") (pintype "bidirectional"))
    )
    (net (code "45") (name "Net-(IC2-A1)") (class "Default")
      (node (ref "IC2") (pin "1") (pinfunction "A1_1") (pintype "bidirectional"))
      (node (ref "R12") (pin "1") (pinfunction "1_1") (pintype "passive"))
    )
    (net (code "46") (name "Net-(IC2-IN-)") (class "Default")
      (node (ref "C6") (pin "1") (pinfunction "1_1") (pintype "passive"))
      (node (ref "IC2") (pin "7") (pinfunction "IN-_7") (pintype "bidirectional"))
      (node (ref "R10") (pin "1") (pinfunction "1_1") (pintype "passive"))
      (node (ref "U$4") (pin "5") (pinfunction "IN_5") (pintype "bidirectional"))
      (node (ref "U$4") (pin "6") (pinfunction "IN_6") (pintype "bidirectional"))
    )
    (net (code "47") (name "Net-(IC3-A0)") (class "Default")
      (node (ref "IC3") (pin "2") (pinfunction "A0_2") (pintype "bidirectional"))
      (node (ref "R30") (pin "1") (pinfunction "1_1") (pintype "passive"))
    )
    (net (code "48") (name "Net-(IC3-IN-)") (class "Default")
      (node (ref "C7") (pin "1") (pinfunction "1_1") (pintype "passive"))
      (node (ref "IC3") (pin "7") (pinfunction "IN-_7") (pintype "bidirectional"))
      (node (ref "R11") (pin "1") (pinfunction "1_1") (pintype "passive"))
      (node (ref "U$5") (pin "5") (pinfunction "IN_5") (pintype "bidirectional"))
      (node (ref "U$5") (pin "6") (pinfunction "IN_6") (pintype "bidirectional"))
    )
    (net (code "49") (name "Net-(IC4-IN-)") (class "Default")
      (node (ref "C11") (pin "1") (pinfunction "1_1") (pintype "passive"))
      (node (ref "IC4") (pin "7") (pinfunction "IN-_7") (pintype "bidirectional"))
      (node (ref "R14") (pin "1") (pinfunction "1_1") (pintype "passive"))
      (node (ref "U$8") (pin "5") (pinfunction "IN_5") (pintype "bidirectional"))
      (node (ref "U$8") (pin "6") (pinfunction "IN_6") (pintype "bidirectional"))
    )
    (net (code "50") (name "Net-(IC5-XTAL1)") (class "Default")
      (node (ref "C25") (pin "1") (pinfunction "1_1") (pintype "passive"))
      (node (ref "IC5") (pin "30") (pinfunction "XTAL1_30") (pintype "bidirectional"))
      (node (ref "Y2") (pin "1") (pinfunction "1_1") (pintype "bidirectional"))
    )
    (net (code "51") (name "Net-(IC5-XTAL2)") (class "Default")
      (node (ref "IC5") (pin "29") (pinfunction "XTAL2_29") (pintype "bidirectional"))
      (node (ref "R16") (pin "2") (pinfunction "2_2") (pintype "passive"))
    )
    (net (code "52") (name "Net-(IC5-~{RESET})") (class "Default")
      (node (ref "C24") (pin "1") (pinfunction "1_1") (pintype "passive"))
      (node (ref "IC5") (pin "4") (pinfunction "~{RESET}_4") (pintype "bidirectional"))
      (node (ref "R15") (pin "2") (pinfunction "2_2") (pintype "passive"))
    )
    (net (code "53") (name "Net-(NEOPIXEL1-DIN)") (class "Default")
      (node (ref "NEOPIXEL1") (pin "4") (pinfunction "DIN_4") (pintype "bidirectional"))
      (node (ref "R6") (pin "1") (pinfunction "1_1") (pintype "passive"))
    )
    (net (code "54") (name "Net-(NEOPIXEL1-DOUT)") (class "Default")
      (node (ref "NEOPIXEL1") (pin "2") (pinfunction "DOUT_2") (pintype "bidirectional"))
      (node (ref "NEOPIXEL2") (pin "4") (pinfunction "DIN_4") (pintype "bidirectional"))
    )
    (net (code "55") (name "Net-(NEOPIXEL2-DOUT)") (class "Default")
      (node (ref "NEOPIXEL2") (pin "2") (pinfunction "DOUT_2") (pintype "bidirectional"))
      (node (ref "NEOPIXEL3") (pin "4") (pinfunction "DIN_4") (pintype "bidirectional"))
    )
    (net (code "56") (name "Net-(NEOPIXEL3-DOUT)") (class "Default")
      (node (ref "NEOPIXEL3") (pin "2") (pinfunction "DOUT_2") (pintype "bidirectional"))
      (node (ref "NEOPIXEL4") (pin "4") (pinfunction "DIN_4") (pintype "bidirectional"))
    )
    (net (code "57") (name "RST") (class "Default")
      (node (ref "IC12") (pin "6") (pinfunction "~{RESET}_6") (pintype "bidirectional"))
      (node (ref "IC7") (pin "RST") (pinfunction "RST_RST") (pintype "input"))
      (node (ref "RESET") (pin "1") (pinfunction "COM_1") (pintype "bidirectional"))
      (node (ref "RN2") (pin "1") (pinfunction "1_1") (pintype "passive"))
    )
    (net (code "58") (name "RX") (class "Default")
      (node (ref "IC7") (pin "RXD/IO3") (pinfunction "RXD/IO3_RXD/IO3") (pintype "bidirectional"))
      (node (ref "PROGRAMMING") (pin "2") (pinfunction "2_2") (pintype "passive"))
    )
    (net (code "59") (name "S1+") (class "Default")
      (node (ref "IC11") (pin "8") (pinfunction "A_8") (pintype "bidirectional"))
      (node (ref "IC6") (pin "6") (pinfunction "2Z_6") (pintype "bidirectional"))
      (node (ref "R2") (pin "2") (pinfunction "2_2") (pintype "passive"))
      (node (ref "R3") (pin "2") (pinfunction "2_2") (pintype "passive"))
    )
    (net (code "60") (name "S1-") (class "Default")
      (node (ref "IC11") (pin "6") (pinfunction "B_6") (pintype "bidirectional"))
      (node (ref "IC6") (pin "1") (pinfunction "1Y_1") (pintype "bidirectional"))
      (node (ref "R1") (pin "2") (pinfunction "2_2") (pintype "passive"))
      (node (ref "R4") (pin "2") (pinfunction "2_2") (pintype "passive"))
    )
    (net (code "61") (name "S2+") (class "Default")
      (node (ref "IC11") (pin "4") (pinfunction "D_4") (pintype "bidirectional"))
      (node (ref "IC13") (pin "6") (pinfunction "2Z_6") (pintype "bidirectional"))
      (node (ref "R17") (pin "2") (pinfunction "2_2") (pintype "passive"))
      (node (ref "R18") (pin "2") (pinfunction "2_2") (pintype "passive"))
    )
    (net (code "62") (name "S2-") (class "Default")
      (node (ref "IC11") (pin "2") (pinfunction "C_2") (pintype "bidirectional"))
      (node (ref "IC13") (pin "1") (pinfunction "1Y_1") (pintype "bidirectional"))
      (node (ref "R13") (pin "2") (pinfunction "2_2") (pintype "passive"))
      (node (ref "R19") (pin "2") (pinfunction "2_2") (pintype "passive"))
    )
    (net (code "63") (name "S3+") (class "Default")
      (node (ref "IC10") (pin "8") (pinfunction "A_8") (pintype "bidirectional"))
      (node (ref "IC14") (pin "6") (pinfunction "2Z_6") (pintype "bidirectional"))
      (node (ref "R23") (pin "2") (pinfunction "2_2") (pintype "passive"))
      (node (ref "R24") (pin "2") (pinfunction "2_2") (pintype "passive"))
    )
    (net (code "64") (name "S3-") (class "Default")
      (node (ref "IC10") (pin "6") (pinfunction "B_6") (pintype "bidirectional"))
      (node (ref "IC14") (pin "1") (pinfunction "1Y_1") (pintype "bidirectional"))
      (node (ref "R20") (pin "2") (pinfunction "2_2") (pintype "passive"))
      (node (ref "R25") (pin "2") (pinfunction "2_2") (pintype "passive"))
    )
    (net (code "65") (name "S4+") (class "Default")
      (node (ref "IC10") (pin "4") (pinfunction "D_4") (pintype "bidirectional"))
      (node (ref "IC15") (pin "6") (pinfunction "2Z_6") (pintype "bidirectional"))
      (node (ref "R27") (pin "2") (pinfunction "2_2") (pintype "passive"))
      (node (ref "R28") (pin "2") (pinfunction "2_2") (pintype "passive"))
    )
    (net (code "66") (name "S4-") (class "Default")
      (node (ref "IC10") (pin "2") (pinfunction "C_2") (pintype "bidirectional"))
      (node (ref "IC15") (pin "1") (pinfunction "1Y_1") (pintype "bidirectional"))
      (node (ref "R26") (pin "2") (pinfunction "2_2") (pintype "passive"))
      (node (ref "R29") (pin "2") (pinfunction "2_2") (pintype "passive"))
    )
    (net (code "67") (name "SCL") (class "Default")
      (node (ref "IC1") (pin "4") (pinfunction "SCL_4") (pintype "bidirectional"))
      (node (ref "IC12") (pin "1") (pinfunction "SCL_1") (pintype "bidirectional"))
      (node (ref "IC2") (pin "4") (pinfunction "SCL_4") (pintype "bidirectional"))
      (node (ref "IC3") (pin "4") (pinfunction "SCL_4") (pintype "bidirectional"))
      (node (ref "IC4") (pin "4") (pinfunction "SCL_4") (pintype "bidirectional"))
      (node (ref "IC7") (pin "IO5") (pinfunction "IO5_IO5") (pintype "bidirectional"))
      (node (ref "OLED") (pin "3") (pinfunction "3_3") (pintype "passive"))
      (node (ref "R21") (pin "1") (pinfunction "1_1") (pintype "passive"))
    )
    (net (code "68") (name "SDA") (class "Default")
      (node (ref "IC1") (pin "3") (pinfunction "SDA_3") (pintype "bidirectional"))
      (node (ref "IC12") (pin "2") (pinfunction "SDA_2") (pintype "bidirectional"))
      (node (ref "IC2") (pin "3") (pinfunction "SDA_3") (pintype "bidirectional"))
      (node (ref "IC3") (pin "3") (pinfunction "SDA_3") (pintype "bidirectional"))
      (node (ref "IC4") (pin "3") (pinfunction "SDA_3") (pintype "bidirectional"))
      (node (ref "IC7") (pin "IO4") (pinfunction "IO4_IO4") (pintype "bidirectional"))
      (node (ref "OLED") (pin "4") (pinfunction "4_4") (pintype "passive"))
      (node (ref "R22") (pin "1") (pinfunction "1_1") (pintype "passive"))
    )
    (net (code "69") (name "TX") (class "Default")
      (node (ref "IC7") (pin "TXD/IO1") (pinfunction "TXD/IO1_TXD/IO1") (pintype "bidirectional"))
      (node (ref "PROGRAMMING") (pin "1") (pinfunction "1_1") (pintype "passive"))
    )
    (net (code "70") (name "VCC") (class "Default")
      (node (ref "C15") (pin "2") (pinfunction "2_2") (pintype "passive"))
      (node (ref "C16") (pin "2") (pinfunction "2_2") (pintype "passive"))
      (node (ref "C19") (pin "1") (pinfunction "1_1") (pintype "passive"))
      (node (ref "C2") (pin "1") (pinfunction "1_1") (pintype "passive"))
      (node (ref "C27") (pin "1") (pinfunction "1_1") (pintype "passive"))
      (node (ref "C3") (pin "1") (pinfunction "1_1") (pintype "passive"))
      (node (ref "C36") (pin "1") (pinfunction "+_1") (pintype "bidirectional"))
      (node (ref "C4") (pin "1") (pinfunction "1_1") (pintype "passive"))
      (node (ref "IC1") (pin "5") (pinfunction "VS_5") (pintype "bidirectional"))
      (node (ref "IC12") (pin "18") (pinfunction "VDD_18") (pintype "bidirectional"))
      (node (ref "IC13") (pin "8") (pinfunction "VCC_8") (pintype "bidirectional"))
      (node (ref "IC14") (pin "8") (pinfunction "VCC_8") (pintype "bidirectional"))
      (node (ref "IC15") (pin "8") (pinfunction "VCC_8") (pintype "bidirectional"))
      (node (ref "IC2") (pin "2") (pinfunction "A0_2") (pintype "bidirectional"))
      (node (ref "IC2") (pin "5") (pinfunction "VS_5") (pintype "bidirectional"))
      (node (ref "IC3") (pin "1") (pinfunction "A1_1") (pintype "bidirectional"))
      (node (ref "IC3") (pin "5") (pinfunction "VS_5") (pintype "bidirectional"))
      (node (ref "IC4") (pin "1") (pinfunction "A1_1") (pintype "bidirectional"))
      (node (ref "IC4") (pin "2") (pinfunction "A0_2") (pintype "bidirectional"))
      (node (ref "IC4") (pin "5") (pinfunction "VS_5") (pintype "bidirectional"))
      (node (ref "IC5") (pin "10") (pinfunction "~{OVRCUR1}_10") (pintype "bidirectional"))
      (node (ref "IC5") (pin "14") (pinfunction "~{OVRCUR2}_14") (pintype "bidirectional"))
      (node (ref "IC5") (pin "18") (pinfunction "~{OVRCUR3}_18") (pintype "bidirectional"))
      (node (ref "IC5") (pin "22") (pinfunction "~{OVRCUR4}_22") (pintype "bidirectional"))
      (node (ref "IC5") (pin "25") (pinfunction "VCC_2_25") (pintype "bidirectional"))
      (node (ref "IC5") (pin "26") (pinfunction "~{EXTMEM}_26") (pintype "bidirectional"))
      (node (ref "IC5") (pin "3") (pinfunction "VCC_1_3") (pintype "bidirectional"))
      (node (ref "IC6") (pin "8") (pinfunction "VCC_8") (pintype "bidirectional"))
      (node (ref "IC7") (pin "EN") (pinfunction "EN_EN") (pintype "bidirectional"))
      (node (ref "IC7") (pin "VCC") (pinfunction "VCC_VCC") (pintype "power_in"))
      (node (ref "IC8") (pin "2") (pinfunction "VOUT_2") (pintype "bidirectional"))
      (node (ref "IC8") (pin "4") (pinfunction "OUTPUT_4") (pintype "bidirectional"))
      (node (ref "NEOPIXEL1") (pin "1") (pinfunction "VDD_1") (pintype "bidirectional"))
      (node (ref "NEOPIXEL2") (pin "1") (pinfunction "VDD_1") (pintype "bidirectional"))
      (node (ref "NEOPIXEL3") (pin "1") (pinfunction "VDD_1") (pintype "bidirectional"))
      (node (ref "NEOPIXEL4") (pin "1") (pinfunction "VDD_1") (pintype "bidirectional"))
      (node (ref "OLED") (pin "2") (pinfunction "2_2") (pintype "passive"))
      (node (ref "R15") (pin "1") (pinfunction "1_1") (pintype "passive"))
      (node (ref "R21") (pin "2") (pinfunction "2_2") (pintype "passive"))
      (node (ref "R22") (pin "2") (pinfunction "2_2") (pintype "passive"))
      (node (ref "R5") (pin "1") (pinfunction "1_1") (pintype "passive"))
      (node (ref "RN2") (pin "6") (pinfunction "2_6") (pintype "passive"))
      (node (ref "RN2") (pin "7") (pinfunction "2_7") (pintype "passive"))
      (node (ref "RN2") (pin "8") (pinfunction "2_8") (pintype "passive"))
      (node (ref "RN3") (pin "5") (pinfunction "2_5") (pintype "passive"))
      (node (ref "RN3") (pin "6") (pinfunction "2_6") (pintype "passive"))
      (node (ref "RN3") (pin "7") (pinfunction "2_7") (pintype "passive"))
      (node (ref "RN3") (pin "8") (pinfunction "2_8") (pintype "passive"))
    )
    (net (code "71") (name "VIN") (class "Default")
      (node (ref "C21") (pin "1") (pinfunction "1_1") (pintype "passive"))
      (node (ref "C22") (pin "1") (pinfunction "1_1") (pintype "passive"))
      (node (ref "IC1") (pin "8") (pinfunction "IN+_8") (pintype "bidirectional"))
      (node (ref "IC2") (pin "8") (pinfunction "IN+_8") (pintype "bidirectional"))
      (node (ref "IC3") (pin "8") (pinfunction "IN+_8") (pintype "bidirectional"))
      (node (ref "IC4") (pin "8") (pinfunction "IN+_8") (pintype "bidirectional"))
      (node (ref "IC8") (pin "3") (pinfunction "VIN_3") (pintype "bidirectional"))
      (node (ref "POWER") (pin "1") (pinfunction "1_1") (pintype "passive"))
      (node (ref "R10") (pin "2") (pinfunction "2_2") (pintype "passive"))
      (node (ref "R11") (pin "2") (pinfunction "2_2") (pintype "passive"))
      (node (ref "R14") (pin "2") (pinfunction "2_2") (pintype "passive"))
      (node (ref "R9") (pin "2") (pinfunction "2_2") (pintype "passive"))
    )
    (net (code "72") (name "unconnected-(IC5-EECLK-Pad5)") (class "Default")
      (node (ref "IC5") (pin "5") (pinfunction "EECLK_5") (pintype "bidirectional"))
    )
    (net (code "73") (name "unconnected-(IC5-EP-Pad33)") (class "Default")
      (node (ref "IC5") (pin "33") (pinfunction "EP_33") (pintype "bidirectional"))
    )
    (net (code "74") (name "unconnected-(IC5-TSTPLL{slash}48MCLK-Pad27)") (class "Default")
      (node (ref "IC5") (pin "27") (pinfunction "TSTPLL/48MCLK_27") (pintype "bidirectional"))
    )
    (net (code "75") (name "unconnected-(IC5-~{PWRON1}-Pad9)") (class "Default")
      (node (ref "IC5") (pin "9") (pinfunction "~{PWRON1}_9") (pintype "bidirectional"))
    )
    (net (code "76") (name "unconnected-(IC5-~{PWRON2}-Pad13)") (class "Default")
      (node (ref "IC5") (pin "13") (pinfunction "~{PWRON2}_13") (pintype "bidirectional"))
    )
    (net (code "77") (name "unconnected-(IC5-~{PWRON3}-Pad17)") (class "Default")
      (node (ref "IC5") (pin "17") (pinfunction "~{PWRON3}_17") (pintype "bidirectional"))
    )
    (net (code "78") (name "unconnected-(IC5-~{PWRON4}-Pad21)") (class "Default")
      (node (ref "IC5") (pin "21") (pinfunction "~{PWRON4}_21") (pintype "bidirectional"))
    )
    (net (code "79") (name "unconnected-(IC7-PadADC)") (class "Default")
      (node (ref "IC7") (pin "ADC") (pinfunction "ADC_ADC") (pintype "bidirectional"))
    )
    (net (code "80") (name "unconnected-(IC7-PadCS0)") (class "Default")
      (node (ref "IC7") (pin "CS0") (pinfunction "CS0_CS0") (pintype "bidirectional"))
    )
    (net (code "81") (name "unconnected-(IC7-PadIO9)") (class "Default")
      (node (ref "IC7") (pin "IO9") (pinfunction "IO9_IO9") (pintype "bidirectional"))
    )
    (net (code "82") (name "unconnected-(IC7-PadIO10)") (class "Default")
      (node (ref "IC7") (pin "IO10") (pinfunction "IO10_IO10") (pintype "bidirectional"))
    )
    (net (code "83") (name "unconnected-(IC7-PadIO16)") (class "Default")
      (node (ref "IC7") (pin "IO16") (pinfunction "IO16_IO16") (pintype "bidirectional"))
    )
    (net (code "84") (name "unconnected-(IC7-PadMISO)") (class "Default")
      (node (ref "IC7") (pin "MISO") (pinfunction "MISO_MISO") (pintype "bidirectional"))
    )
    (net (code "85") (name "unconnected-(IC7-PadMOSI)") (class "Default")
      (node (ref "IC7") (pin "MOSI") (pinfunction "MOSI_MOSI") (pintype "bidirectional"))
    )
    (net (code "86") (name "unconnected-(IC7-PadSCLK)") (class "Default")
      (node (ref "IC7") (pin "SCLK") (pinfunction "SCLK_SCLK") (pintype "bidirectional"))
    )
    (net (code "87") (name "unconnected-(IC9-A-Pad8)") (class "Default")
      (node (ref "IC9") (pin "8") (pinfunction "A_8") (pintype "bidirectional"))
    )
    (net (code "88") (name "unconnected-(IC9-B-Pad6)") (class "Default")
      (node (ref "IC9") (pin "6") (pinfunction "B_6") (pintype "bidirectional"))
    )
    (net (code "89") (name "unconnected-(IC9-GND_3-Pad5)") (class "Default")
      (node (ref "IC9") (pin "5") (pinfunction "GND_3_5") (pintype "bidirectional"))
    )
    (net (code "90") (name "unconnected-(IC9-GND_4-Pad7)") (class "Default")
      (node (ref "IC9") (pin "7") (pinfunction "GND_4_7") (pintype "bidirectional"))
    )
    (net (code "91") (name "unconnected-(IC12-NC-Pad7)") (class "Default")
      (node (ref "IC12") (pin "7") (pinfunction "NC_7") (pintype "no_connect"))
    )
    (net (code "92") (name "unconnected-(NEOPIXEL4-DOUT-Pad2)") (class "Default")
      (node (ref "NEOPIXEL4") (pin "2") (pinfunction "DOUT_2") (pintype "bidirectional"))
    )
    (net (code "93") (name "unconnected-(RN1D-2-Pad5)") (class "Default")
      (node (ref "RN1") (pin "5") (pinfunction "2_5") (pintype "passive"))
    )
    (net (code "94") (name "unconnected-(RN3-Pad1)") (class "Default")
      (node (ref "RN3") (pin "1") (pinfunction "1_1") (pintype "passive"))
    )
    (net (code "95") (name "unconnected-(USBIN-PadVBUS)") (class "Default")
      (node (ref "USBIN") (pin "VBUS") (pinfunction "VBUS_VBUS") (pintype "bidirectional"))
    )
  )
)
